# monitoring.net
KiCad netlist of a schematic drawn in Altium Designer
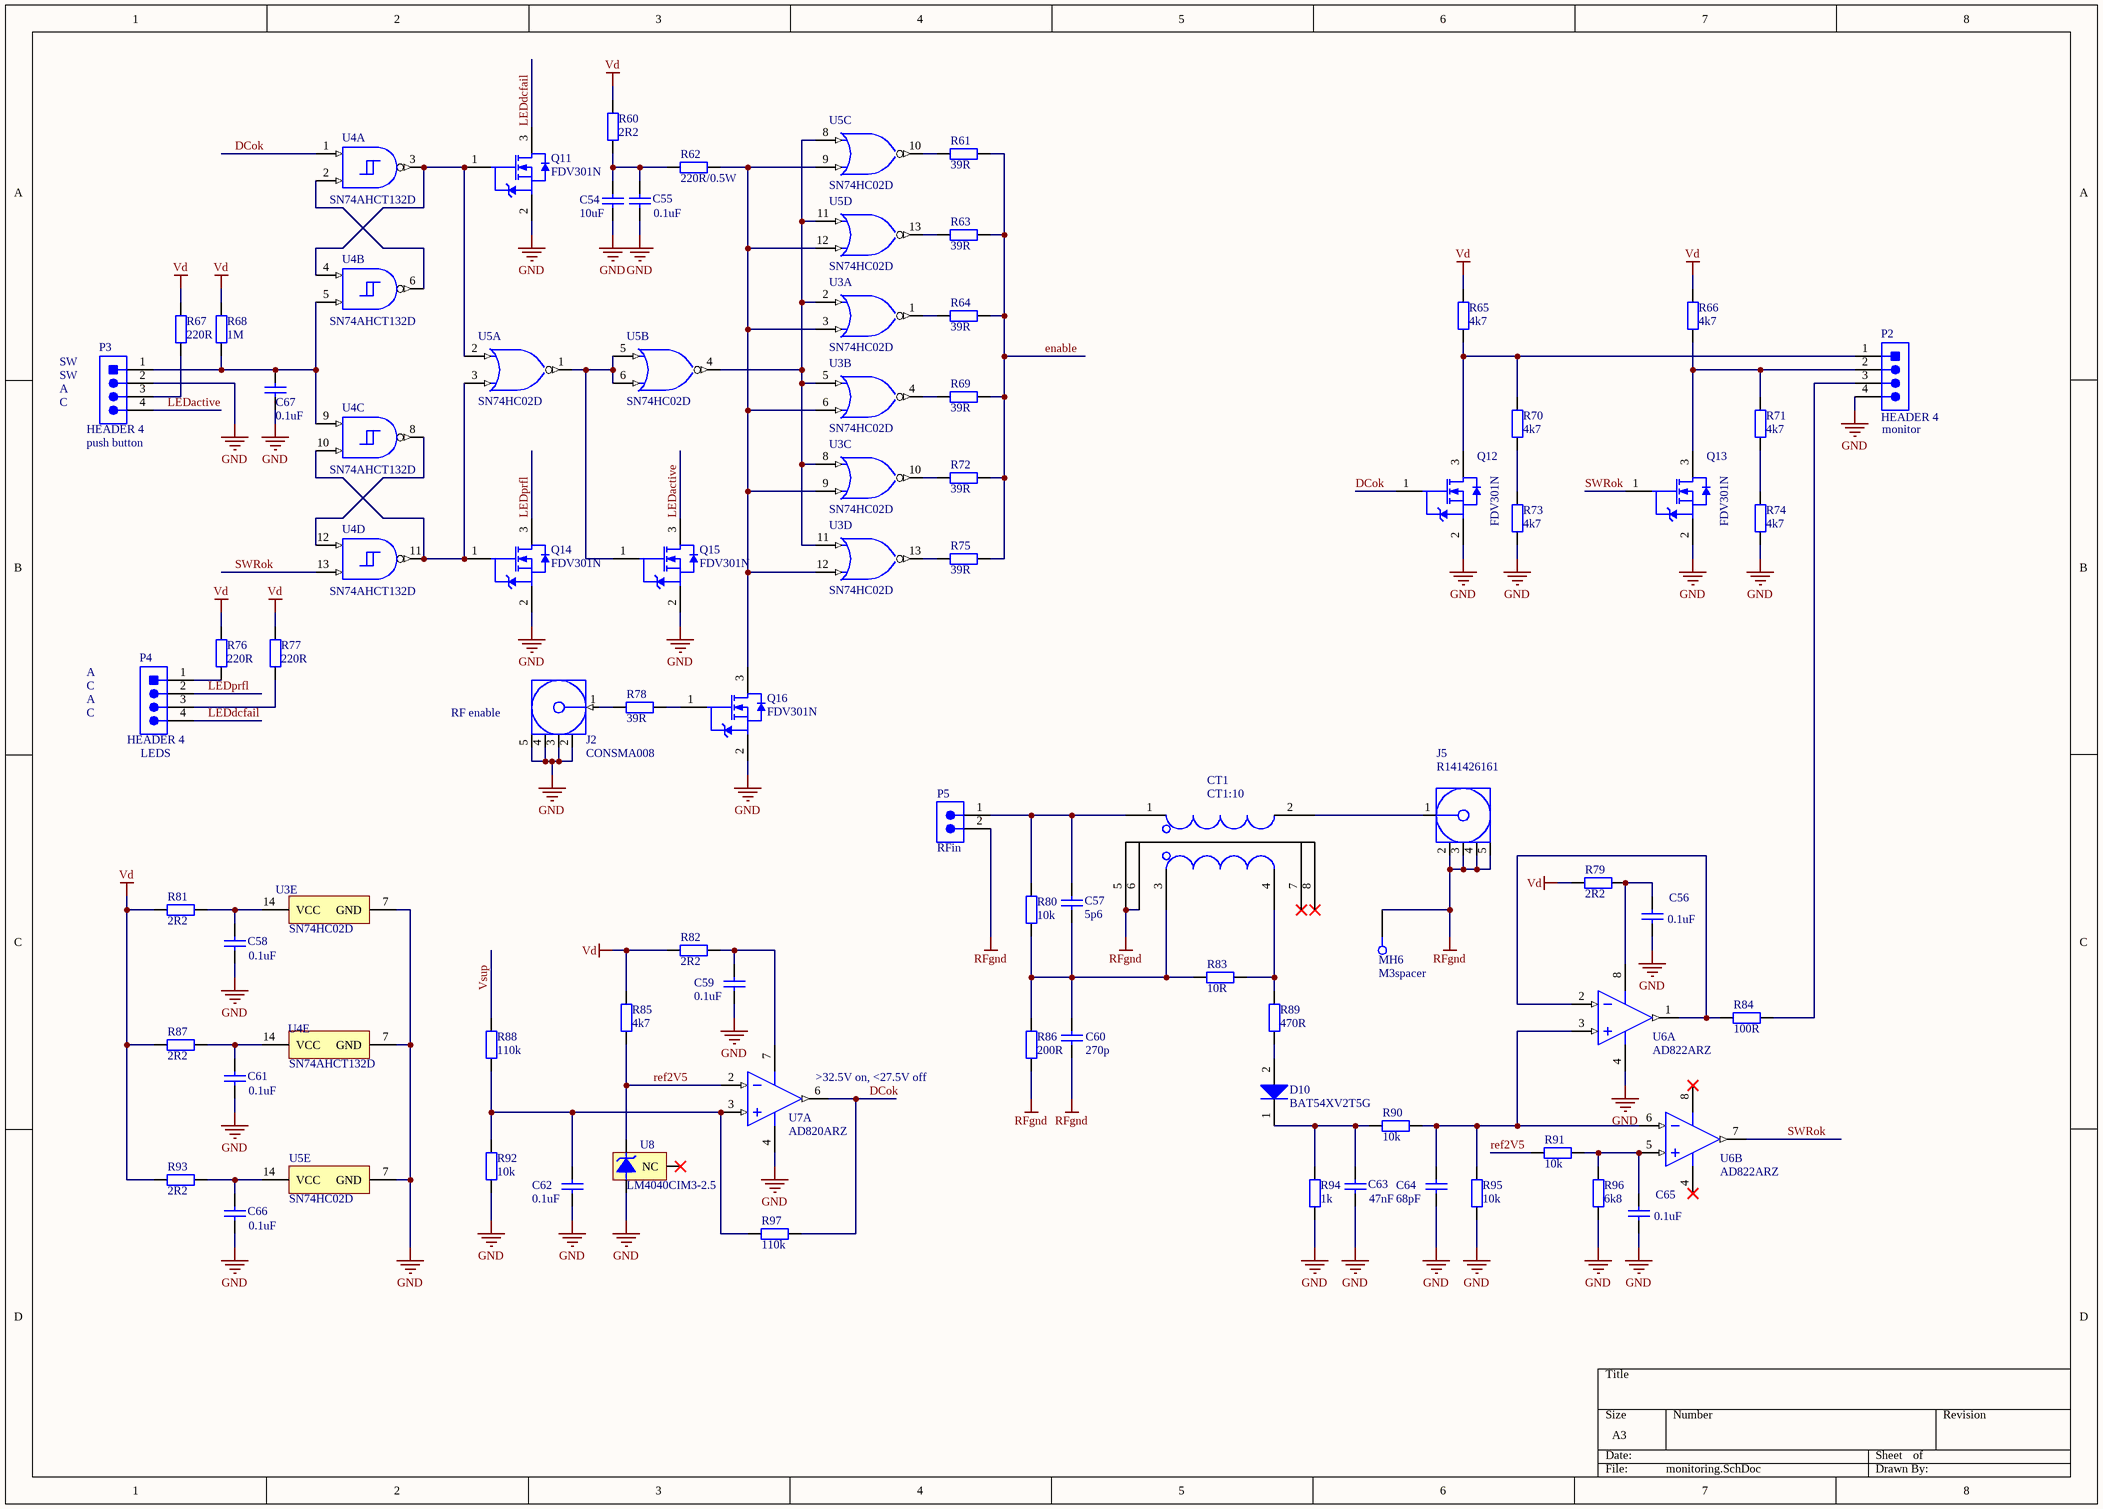
[diagram p0: monitoring.SchDoc]

(export (version "E")
  (design (tool "Eeschema 10.0.6"))
  (components
    (comp (ref "C54")
      (value "10uF")
      (footprint "sm:SM/C_1210")
      (description "Capacitor")
      (fields (field (name "Comment") "Cap") (field (name "PUBLISHER") "Altium Limited"))
      (libsource (lib "Miscellaneous Devices") (part "Cap"))
    )
    (comp (ref "C55")
      (value "0.1uF")
      (footprint "sm:SM/C_0805")
      (description "Capacitor")
      (fields (field (name "Comment") "Cap") (field (name "PUBLISHER") "Altium Limited"))
      (libsource (lib "Miscellaneous Devices") (part "Cap"))
    )
    (comp (ref "C56")
      (value "0.1uF")
      (footprint "sm:SM/C_0805")
      (description "Capacitor")
      (fields (field (name "Comment") "Cap") (field (name "PUBLISHER") "Altium Limited"))
      (libsource (lib "Miscellaneous Devices") (part "Cap"))
    )
    (comp (ref "C57")
      (value "5p6")
      (footprint "sm:SM/C_1206")
      (description "Capacitor")
      (fields (field (name "Comment") "Cap") (field (name "PUBLISHER") "Altium Limited"))
      (libsource (lib "Miscellaneous Devices") (part "Cap"))
    )
    (comp (ref "C58")
      (value "0.1uF")
      (footprint "sm:SM/C_0805")
      (description "Capacitor")
      (fields (field (name "Comment") "Cap") (field (name "PUBLISHER") "Altium Limited"))
      (libsource (lib "Miscellaneous Devices") (part "Cap"))
    )
    (comp (ref "C59")
      (value "0.1uF")
      (footprint "sm:SM/C_0805")
      (description "Capacitor")
      (fields (field (name "Comment") "Cap") (field (name "PUBLISHER") "Altium Limited"))
      (libsource (lib "Miscellaneous Devices") (part "Cap"))
    )
    (comp (ref "C60")
      (value "270p")
      (footprint "sm:SM/C_0805")
      (description "Capacitor")
      (fields (field (name "Comment") "Cap") (field (name "PUBLISHER") "Altium Limited"))
      (libsource (lib "Miscellaneous Devices") (part "Cap"))
    )
    (comp (ref "C61")
      (value "0.1uF")
      (footprint "sm:SM/C_0805")
      (description "Capacitor")
      (fields (field (name "Comment") "Cap") (field (name "PUBLISHER") "Altium Limited"))
      (libsource (lib "Miscellaneous Devices") (part "Cap"))
    )
    (comp (ref "C62")
      (value "0.1uF")
      (footprint "sm:SM/C_0805")
      (description "Capacitor")
      (fields (field (name "Comment") "Cap") (field (name "PUBLISHER") "Altium Limited"))
      (libsource (lib "Miscellaneous Devices") (part "Cap"))
    )
    (comp (ref "C63")
      (value "47nF")
      (footprint "sm:SM/C_0805")
      (description "Capacitor")
      (fields (field (name "Comment") "Cap") (field (name "PUBLISHER") "Altium Limited"))
      (libsource (lib "Miscellaneous Devices") (part "Cap"))
    )
    (comp (ref "C64")
      (value "68pF")
      (footprint "sm:SM/C_0805")
      (description "Capacitor")
      (fields (field (name "Comment") "Cap") (field (name "PUBLISHER") "Altium Limited"))
      (libsource (lib "Miscellaneous Devices") (part "Cap"))
    )
    (comp (ref "C65")
      (value "0.1uF")
      (footprint "sm:SM/C_0805")
      (description "Capacitor")
      (fields (field (name "Comment") "Cap") (field (name "PUBLISHER") "Altium Limited"))
      (libsource (lib "Miscellaneous Devices") (part "Cap"))
    )
    (comp (ref "C66")
      (value "0.1uF")
      (footprint "sm:SM/C_0805")
      (description "Capacitor")
      (fields (field (name "Comment") "Cap") (field (name "PUBLISHER") "Altium Limited"))
      (libsource (lib "Miscellaneous Devices") (part "Cap"))
    )
    (comp (ref "C67")
      (value "0.1uF")
      (footprint "sm:SM/C_0805")
      (description "Capacitor")
      (fields (field (name "Comment") "Cap") (field (name "PUBLISHER") "Altium Limited"))
      (libsource (lib "Miscellaneous Devices") (part "Cap"))
    )
    (comp (ref "CT1") (value "CT1:10") (libsource (lib "stroomtrafo") (part "Component_1")))
    (comp (ref "D10")
      (value "BAT54XV2T5G")
      (footprint "ONSC-SOD-523-2-502-01_V")
      (description "Schottky Barrier Diode, 2-Pin SOD-523, Pb-Free, Tape and Reel")
      (fields (field (name "MANUFACTURER") "On Semiconductor"))
      (libsource (lib "Altium Content Vault") (part "CMP-1055-00490-1"))
    )
    (comp (ref "J2")
      (value "CONSMA008")
      (footprint "Footprint Library:SMA-Grotere-Gaten")
      (description "SMA Female PCB Mount Connector - Extended")
      (libsource (lib "altium-import") (part "root_0_mirrored_CMP-0168-00003-1_"))
    )
    (comp (ref "J5")
      (value "R141426161")
      (footprint "Footprint Library:BNC_Danny")
      (description "Jack BNC Connector, 1 Position, Height 16.26 mm, Tail Length 6.35 mm, -55 to 85 degC, RoHS, Tube")
      (fields (field (name "MANUFACTURER") "TE Connectivity"))
      (libsource (lib "altium-import") (part "root_0_CMP-2000-05627-1_"))
    )
    (comp (ref "MH6")
      (value "M3spacer")
      (footprint "CSTEMP:MTHOLE3.2MM_TOPBOT7MM")
      (description "Mounting Hole, Embedded System Module, 3.2mm pad, 2.7mm plated hole, Top / Bottom copper regions")
      (fields (field (name "PUBLISHER") "Altium"))
      (libsource (lib "altium-import") (part "root_2_MH_"))
    )
    (comp (ref "P2")
      (value "HEADER 4")
      (footprint "pcon100t:POLCON.100/VH/TM1SQS/W.300/4")
      (libsource (lib "altium-import") (part "root_0_CMP-1755-00007-1_"))
    )
    (comp (ref "P3")
      (value "HEADER 4")
      (footprint "pcon100t:POLCON.100/VH/TM1SQS/W.300/4")
      (libsource (lib "altium-import") (part "root_0_mirrored_CMP-1755-00007-1_"))
    )
    (comp (ref "P4")
      (value "HEADER 4")
      (footprint "pcon100t:POLCON.100/VH/TM1SQS/W.300/4")
      (libsource (lib "altium-import") (part "root_0_mirrored_CMP-1755-00007-1_"))
    )
    (comp (ref "P5")
      (value "RFin")
      (footprint "MRIamp:megaheader")
      (fields
        (field (name "MANUFACTURER") "GCT")
        (field (name "PARTNUMBER") "BG055-02-A-1-0650-0530-0350-L-B")
      )
      (libsource (lib "altium-import") (part "root_3_mirrored_CMP-0815-00001-1_"))
    )
    (comp (ref "Q11")
      (value "FDV301N")
      (footprint "FAIR-SOT23-3_V")
      (description "Digital FET, N-Channel, 0.35 W, 25 V, -55 to 150 degC, 3-Pin SOT23, RoHS, Tape and Reel")
      (fields (field (name "MANUFACTURER") "Fairchild"))
      (libsource (lib "Altium Content Vault") (part "CMP-2000-04935-1"))
    )
    (comp (ref "Q12")
      (value "FDV301N")
      (footprint "FAIR-SOT23-3_V")
      (description "Digital FET, N-Channel, 0.35 W, 25 V, -55 to 150 degC, 3-Pin SOT23, RoHS, Tape and Reel")
      (fields (field (name "MANUFACTURER") "Fairchild"))
      (libsource (lib "Altium Content Vault") (part "CMP-2000-04935-1"))
    )
    (comp (ref "Q13")
      (value "FDV301N")
      (footprint "FAIR-SOT23-3_V")
      (description "Digital FET, N-Channel, 0.35 W, 25 V, -55 to 150 degC, 3-Pin SOT23, RoHS, Tape and Reel")
      (fields (field (name "MANUFACTURER") "Fairchild"))
      (libsource (lib "Altium Content Vault") (part "CMP-2000-04935-1"))
    )
    (comp (ref "Q14")
      (value "FDV301N")
      (footprint "FAIR-SOT23-3_V")
      (description "Digital FET, N-Channel, 0.35 W, 25 V, -55 to 150 degC, 3-Pin SOT23, RoHS, Tape and Reel")
      (fields (field (name "MANUFACTURER") "Fairchild"))
      (libsource (lib "Altium Content Vault") (part "CMP-2000-04935-1"))
    )
    (comp (ref "Q15")
      (value "FDV301N")
      (footprint "FAIR-SOT23-3_V")
      (description "Digital FET, N-Channel, 0.35 W, 25 V, -55 to 150 degC, 3-Pin SOT23, RoHS, Tape and Reel")
      (fields (field (name "MANUFACTURER") "Fairchild"))
      (libsource (lib "Altium Content Vault") (part "CMP-2000-04935-1"))
    )
    (comp (ref "Q16")
      (value "FDV301N")
      (footprint "FAIR-SOT23-3_V")
      (description "Digital FET, N-Channel, 0.35 W, 25 V, -55 to 150 degC, 3-Pin SOT23, RoHS, Tape and Reel")
      (fields (field (name "MANUFACTURER") "Fairchild"))
      (libsource (lib "Altium Content Vault") (part "CMP-2000-04935-1"))
    )
    (comp (ref "R60")
      (value "2R2")
      (footprint "sm:SM/R_0805")
      (description "Resistor")
      (fields (field (name "Comment") "Res2") (field (name "PUBLISHER") "Altium Limited"))
      (libsource (lib "Miscellaneous Devices") (part "Res2"))
    )
    (comp (ref "R61")
      (value "39R")
      (footprint "sm:SM/R_0805")
      (description "Resistor")
      (fields (field (name "Comment") "Res2") (field (name "PUBLISHER") "Altium Limited"))
      (libsource (lib "") (part "Res2_2"))
    )
    (comp (ref "R62")
      (value "220R/0.5W")
      (footprint "sm:SM/R_1210")
      (description "Resistor")
      (fields (field (name "Comment") "Res2") (field (name "PUBLISHER") "Altium Limited"))
      (libsource (lib "") (part "Res2_1"))
    )
    (comp (ref "R63")
      (value "39R")
      (footprint "sm:SM/R_0805")
      (description "Resistor")
      (fields (field (name "Comment") "Res2") (field (name "PUBLISHER") "Altium Limited"))
      (libsource (lib "") (part "Res2_2"))
    )
    (comp (ref "R64")
      (value "39R")
      (footprint "sm:SM/R_0805")
      (description "Resistor")
      (fields (field (name "Comment") "Res2") (field (name "PUBLISHER") "Altium Limited"))
      (libsource (lib "") (part "Res2_2"))
    )
    (comp (ref "R65")
      (value "4k7")
      (footprint "sm:SM/R_0805")
      (description "Resistor")
      (fields (field (name "Comment") "Res2") (field (name "PUBLISHER") "Altium Limited"))
      (libsource (lib "Miscellaneous Devices") (part "Res2"))
    )
    (comp (ref "R66")
      (value "4k7")
      (footprint "sm:SM/R_0805")
      (description "Resistor")
      (fields (field (name "Comment") "Res2") (field (name "PUBLISHER") "Altium Limited"))
      (libsource (lib "Miscellaneous Devices") (part "Res2"))
    )
    (comp (ref "R67")
      (value "220R")
      (footprint "sm:SM/C_1206")
      (description "Resistor")
      (fields (field (name "Comment") "Res2") (field (name "PUBLISHER") "Altium Limited"))
      (libsource (lib "Miscellaneous Devices") (part "Res2"))
    )
    (comp (ref "R68")
      (value "1M")
      (footprint "sm:SM/R_0805")
      (description "Resistor")
      (fields (field (name "Comment") "Res2") (field (name "PUBLISHER") "Altium Limited"))
      (libsource (lib "Miscellaneous Devices") (part "Res2"))
    )
    (comp (ref "R69")
      (value "39R")
      (footprint "sm:SM/R_0805")
      (description "Resistor")
      (fields (field (name "Comment") "Res2") (field (name "PUBLISHER") "Altium Limited"))
      (libsource (lib "") (part "Res2_2"))
    )
    (comp (ref "R70")
      (value "4k7")
      (footprint "sm:SM/R_0805")
      (description "Resistor")
      (fields (field (name "Comment") "Res2") (field (name "PUBLISHER") "Altium Limited"))
      (libsource (lib "Miscellaneous Devices") (part "Res2"))
    )
    (comp (ref "R71")
      (value "4k7")
      (footprint "sm:SM/R_0805")
      (description "Resistor")
      (fields (field (name "Comment") "Res2") (field (name "PUBLISHER") "Altium Limited"))
      (libsource (lib "Miscellaneous Devices") (part "Res2"))
    )
    (comp (ref "R72")
      (value "39R")
      (footprint "sm:SM/R_0805")
      (description "Resistor")
      (fields (field (name "Comment") "Res2") (field (name "PUBLISHER") "Altium Limited"))
      (libsource (lib "") (part "Res2_2"))
    )
    (comp (ref "R73")
      (value "4k7")
      (footprint "sm:SM/R_0805")
      (description "Resistor")
      (fields (field (name "Comment") "Res2") (field (name "PUBLISHER") "Altium Limited"))
      (libsource (lib "Miscellaneous Devices") (part "Res2"))
    )
    (comp (ref "R74")
      (value "4k7")
      (footprint "sm:SM/R_0805")
      (description "Resistor")
      (fields (field (name "Comment") "Res2") (field (name "PUBLISHER") "Altium Limited"))
      (libsource (lib "Miscellaneous Devices") (part "Res2"))
    )
    (comp (ref "R75")
      (value "39R")
      (footprint "sm:SM/R_0805")
      (description "Resistor")
      (fields (field (name "Comment") "Res2") (field (name "PUBLISHER") "Altium Limited"))
      (libsource (lib "") (part "Res2_2"))
    )
    (comp (ref "R76")
      (value "220R")
      (footprint "sm:SM/C_1206")
      (description "Resistor")
      (fields (field (name "Comment") "Res2") (field (name "PUBLISHER") "Altium Limited"))
      (libsource (lib "Miscellaneous Devices") (part "Res2"))
    )
    (comp (ref "R77")
      (value "220R")
      (footprint "sm:SM/C_1206")
      (description "Resistor")
      (fields (field (name "Comment") "Res2") (field (name "PUBLISHER") "Altium Limited"))
      (libsource (lib "Miscellaneous Devices") (part "Res2"))
    )
    (comp (ref "R78")
      (value "39R")
      (footprint "sm:SM/R_0805")
      (description "Resistor")
      (fields (field (name "Comment") "Res2") (field (name "PUBLISHER") "Altium Limited"))
      (libsource (lib "") (part "Res2_2"))
    )
    (comp (ref "R79")
      (value "2R2")
      (footprint "sm:SM/R_0805")
      (description "Resistor")
      (fields (field (name "Comment") "Res2") (field (name "PUBLISHER") "Altium Limited"))
      (libsource (lib "") (part "Res2_2"))
    )
    (comp (ref "R80")
      (value "10k")
      (footprint "tm_axial:AX/.800X.200/.037")
      (description "Resistor")
      (fields (field (name "Comment") "Res2") (field (name "PUBLISHER") "Altium Limited"))
      (libsource (lib "Miscellaneous Devices") (part "Res2"))
    )
    (comp (ref "R81")
      (value "2R2")
      (footprint "sm:SM/R_0805")
      (description "Resistor")
      (fields (field (name "Comment") "Res2") (field (name "PUBLISHER") "Altium Limited"))
      (libsource (lib "") (part "Res2_2"))
    )
    (comp (ref "R82")
      (value "2R2")
      (footprint "sm:SM/R_0805")
      (description "Resistor")
      (fields (field (name "Comment") "Res2") (field (name "PUBLISHER") "Altium Limited"))
      (libsource (lib "") (part "Res2_2"))
    )
    (comp (ref "R83")
      (value "10R")
      (footprint "tm_axial:AX/.800X.200/.037")
      (description "Resistor")
      (fields (field (name "Comment") "Res2") (field (name "PUBLISHER") "Altium Limited"))
      (libsource (lib "") (part "Res2_1"))
    )
    (comp (ref "R84")
      (value "100R")
      (footprint "sm:SM/C_1206")
      (description "Resistor")
      (fields (field (name "Comment") "Res2") (field (name "PUBLISHER") "Altium Limited"))
      (libsource (lib "") (part "Res2_1"))
    )
    (comp (ref "R85")
      (value "4k7")
      (footprint "sm:SM/R_0805")
      (description "Resistor")
      (fields (field (name "Comment") "Res2") (field (name "PUBLISHER") "Altium Limited"))
      (libsource (lib "Miscellaneous Devices") (part "Res2"))
    )
    (comp (ref "R86")
      (value "200R")
      (footprint "tm_axial:AX/.550X.150/.034")
      (description "Resistor")
      (fields (field (name "Comment") "Res2") (field (name "PUBLISHER") "Altium Limited"))
      (libsource (lib "Miscellaneous Devices") (part "Res2"))
    )
    (comp (ref "R87")
      (value "2R2")
      (footprint "sm:SM/R_0805")
      (description "Resistor")
      (fields (field (name "Comment") "Res2") (field (name "PUBLISHER") "Altium Limited"))
      (libsource (lib "") (part "Res2_2"))
    )
    (comp (ref "R88")
      (value "110k")
      (footprint "sm:SM/R_0805")
      (description "Resistor")
      (fields (field (name "Comment") "Res2") (field (name "PUBLISHER") "Altium Limited"))
      (libsource (lib "Miscellaneous Devices") (part "Res2"))
    )
    (comp (ref "R89")
      (value "470R")
      (footprint "sm:SM/R_0805")
      (description "Resistor")
      (fields (field (name "Comment") "Res2") (field (name "PUBLISHER") "Altium Limited"))
      (libsource (lib "Miscellaneous Devices") (part "Res2"))
    )
    (comp (ref "R90")
      (value "10k")
      (footprint "sm:SM/R_0805")
      (description "Resistor")
      (fields (field (name "Comment") "Res2") (field (name "PUBLISHER") "Altium Limited"))
      (libsource (lib "") (part "Res2_2"))
    )
    (comp (ref "R91")
      (value "10k")
      (footprint "sm:SM/R_0805")
      (description "Resistor")
      (fields (field (name "Comment") "Res2") (field (name "PUBLISHER") "Altium Limited"))
      (libsource (lib "") (part "Res2_2"))
    )
    (comp (ref "R92")
      (value "10k")
      (footprint "sm:SM/R_0805")
      (description "Resistor")
      (fields (field (name "Comment") "Res2") (field (name "PUBLISHER") "Altium Limited"))
      (libsource (lib "Miscellaneous Devices") (part "Res2"))
    )
    (comp (ref "R93")
      (value "2R2")
      (footprint "sm:SM/R_0805")
      (description "Resistor")
      (fields (field (name "Comment") "Res2") (field (name "PUBLISHER") "Altium Limited"))
      (libsource (lib "") (part "Res2_2"))
    )
    (comp (ref "R94")
      (value "1k")
      (footprint "sm:SM/R_0805")
      (description "Resistor")
      (fields (field (name "Comment") "Res2") (field (name "PUBLISHER") "Altium Limited"))
      (libsource (lib "Miscellaneous Devices") (part "Res2"))
    )
    (comp (ref "R95")
      (value "10k")
      (footprint "sm:SM/R_0805")
      (description "Resistor")
      (fields (field (name "Comment") "Res2") (field (name "PUBLISHER") "Altium Limited"))
      (libsource (lib "") (part "Res2_3"))
    )
    (comp (ref "R96")
      (value "6k8")
      (footprint "sm:SM/R_0805")
      (description "Resistor")
      (fields (field (name "Comment") "Res2") (field (name "PUBLISHER") "Altium Limited"))
      (libsource (lib "") (part "Res2_3"))
    )
    (comp (ref "R97")
      (value "110k")
      (footprint "sm:SM/R_0805")
      (description "Resistor")
      (fields (field (name "Comment") "Res2") (field (name "PUBLISHER") "Altium Limited"))
      (libsource (lib "") (part "Res2_2"))
    )
    (comp (ref "U3")
      (value "SN74HC02D")
      (footprint "D0014A_N")
      (description "Quadruple 2-Input Positive-NOR Gates, D0014A, TUBE")
      (fields
        (field (name "GENERIC PART NUMBER") "SN74HC02")
        (field (name "MANUFACTURER") "Texas Instruments")
      )
      (libsource (lib "Altium Content Vault") (part "CMP-0806-00060-3"))
    )
    (comp (ref "U4")
      (value "SN74AHCT132D")
      (footprint "D0014A_L")
      (description "Quadruple Positive-NAND Gates With Schmitt-Trigger Inputs, D0014A, TUBE")
      (fields
        (field (name "GENERIC PART NUMBER") "SN74AHCT132")
        (field (name "MANUFACTURER") "Texas Instruments")
      )
      (libsource (lib "Altium Content Vault") (part "CMP-1627-00035-3"))
    )
    (comp (ref "U5")
      (value "SN74HC02D")
      (footprint "D0014A_N")
      (description "Quadruple 2-Input Positive-NOR Gates, D0014A, TUBE")
      (fields
        (field (name "GENERIC PART NUMBER") "SN74HC02")
        (field (name "MANUFACTURER") "Texas Instruments")
      )
      (libsource (lib "Altium Content Vault") (part "CMP-0806-00060-3"))
    )
    (comp (ref "U6")
      (value "AD822ARZ")
      (footprint "ADI-R-8_M")
      (fields (field (name "MANUFACTURER") "Analog Devices") (field (name "GENERIC PART NUMBER") "AD822"))
      (libsource (lib "Altium Content Vault") (part "CMP-0384-00785-2"))
    )
    (comp (ref "U7")
      (value "AD820ARZ")
      (footprint "ADI-R-8_L")
      (fields
        (field (name "PARTNUMBER") "AD820ARZ-REEL7")
        (field (name "GENERIC PART NUMBER") "AD820")
        (field (name "MANUFACTURER") "Analog Devices")
      )
      (libsource (lib "Altium Content Vault") (part "CMP-0384-00651-1"))
    )
    (comp (ref "U8")
      (value "LM4040CIM3-2.5")
      (footprint "DBZ0003A_N")
      (description "Precision Micropower Shunt Voltage Reference, 3-pin SOT-23")
      (fields (field (name "MANUFACTURER") "Texas Instruments"))
      (libsource (lib "Altium Content Vault") (part "CMP-0074-00570-3"))
    )
  )
  (nets
    (net (code "1") (name "/DCok") (class "Default")
      (node (ref "Q12") (pin "1") (pinfunction "G_1") (pintype "passive"))
      (node (ref "R97") (pin "2") (pinfunction "2_2") (pintype "passive"))
      (node (ref "U4") (pin "1") (pinfunction "1A_1") (pintype "input"))
      (node (ref "U7") (pin "6") (pinfunction "VOUT_6") (pintype "output"))
    )
    (net (code "2") (name "/LEDactive") (class "Default")
      (node (ref "P3") (pin "4") (pinfunction "4_4") (pintype "passive"))
      (node (ref "Q15") (pin "3") (pinfunction "D_3") (pintype "passive"))
    )
    (net (code "3") (name "/LEDdcfail") (class "Default")
      (node (ref "P4") (pin "4") (pinfunction "4_4") (pintype "passive"))
      (node (ref "Q11") (pin "3") (pinfunction "D_3") (pintype "passive"))
    )
    (net (code "4") (name "/LEDprfl") (class "Default")
      (node (ref "P4") (pin "2") (pinfunction "2_2") (pintype "passive"))
      (node (ref "Q14") (pin "3") (pinfunction "D_3") (pintype "passive"))
    )
    (net (code "5") (name "/SWRok") (class "Default")
      (node (ref "Q13") (pin "1") (pinfunction "G_1") (pintype "passive"))
      (node (ref "U4") (pin "13") (pinfunction "4B_13") (pintype "input"))
      (node (ref "U6") (pin "7") (pinfunction "OUT_2_7") (pintype "output"))
    )
    (net (code "6") (name "/Vsup") (class "Default")
      (node (ref "R88") (pin "1") (pinfunction "1_1") (pintype "passive"))
    )
    (net (code "7") (name "/enable") (class "Default")
      (node (ref "R61") (pin "2") (pinfunction "2_2") (pintype "passive"))
      (node (ref "R63") (pin "2") (pinfunction "2_2") (pintype "passive"))
      (node (ref "R64") (pin "2") (pinfunction "2_2") (pintype "passive"))
      (node (ref "R69") (pin "2") (pinfunction "2_2") (pintype "passive"))
      (node (ref "R72") (pin "2") (pinfunction "2_2") (pintype "passive"))
      (node (ref "R75") (pin "2") (pinfunction "2_2") (pintype "passive"))
    )
    (net (code "8") (name "/ref2V5") (class "Default")
      (node (ref "R85") (pin "2") (pinfunction "2_2") (pintype "passive"))
      (node (ref "R91") (pin "1") (pinfunction "1_1") (pintype "passive"))
      (node (ref "U7") (pin "2") (pinfunction "-IN_2") (pintype "input"))
      (node (ref "U8") (pin "1") (pinfunction "+V_1") (pintype "passive"))
    )
    (net (code "9") (name "GND") (class "Default")
      (node (ref "C54") (pin "2") (pinfunction "2_2") (pintype "passive"))
      (node (ref "C55") (pin "1") (pinfunction "1_1") (pintype "passive"))
      (node (ref "C56") (pin "1") (pinfunction "1_1") (pintype "passive"))
      (node (ref "C58") (pin "1") (pinfunction "1_1") (pintype "passive"))
      (node (ref "C59") (pin "1") (pinfunction "1_1") (pintype "passive"))
      (node (ref "C61") (pin "1") (pinfunction "1_1") (pintype "passive"))
      (node (ref "C62") (pin "1") (pinfunction "1_1") (pintype "passive"))
      (node (ref "C63") (pin "1") (pinfunction "1_1") (pintype "passive"))
      (node (ref "C64") (pin "1") (pinfunction "1_1") (pintype "passive"))
      (node (ref "C65") (pin "1") (pinfunction "1_1") (pintype "passive"))
      (node (ref "C66") (pin "1") (pinfunction "1_1") (pintype "passive"))
      (node (ref "C67") (pin "1") (pinfunction "1_1") (pintype "passive"))
      (node (ref "J2") (pin "2") (pinfunction "GND_2") (pintype "power_in"))
      (node (ref "J2") (pin "3") (pinfunction "GND_3") (pintype "power_in"))
      (node (ref "J2") (pin "4") (pinfunction "GND_4") (pintype "power_in"))
      (node (ref "J2") (pin "5") (pinfunction "GND_5") (pintype "power_in"))
      (node (ref "P2") (pin "4") (pinfunction "4_4") (pintype "passive"))
      (node (ref "P3") (pin "2") (pinfunction "2_2") (pintype "passive"))
      (node (ref "Q11") (pin "2") (pinfunction "S_2") (pintype "passive"))
      (node (ref "Q12") (pin "2") (pinfunction "S_2") (pintype "passive"))
      (node (ref "Q13") (pin "2") (pinfunction "S_2") (pintype "passive"))
      (node (ref "Q14") (pin "2") (pinfunction "S_2") (pintype "passive"))
      (node (ref "Q15") (pin "2") (pinfunction "S_2") (pintype "passive"))
      (node (ref "Q16") (pin "2") (pinfunction "S_2") (pintype "passive"))
      (node (ref "R73") (pin "2") (pinfunction "2_2") (pintype "passive"))
      (node (ref "R74") (pin "2") (pinfunction "2_2") (pintype "passive"))
      (node (ref "R92") (pin "2") (pinfunction "2_2") (pintype "passive"))
      (node (ref "R94") (pin "2") (pinfunction "2_2") (pintype "passive"))
      (node (ref "R95") (pin "1") (pinfunction "1_1") (pintype "passive"))
      (node (ref "R96") (pin "1") (pinfunction "1_1") (pintype "passive"))
      (node (ref "U3") (pin "7") (pinfunction "GND_7") (pintype "power_in"))
      (node (ref "U4") (pin "7") (pinfunction "GND_7") (pintype "power_in"))
      (node (ref "U5") (pin "7") (pinfunction "GND_7") (pintype "power_in"))
      (node (ref "U6") (pin "4") (pinfunction "-V_4") (pintype "power_in"))
      (node (ref "U7") (pin "4") (pinfunction "-VS_4") (pintype "power_in"))
      (node (ref "U8") (pin "2") (pinfunction "-V_2") (pintype "passive"))
    )
    (net (code "10") (name "Net-(C54-Pad1)") (class "Default")
      (node (ref "C54") (pin "1") (pinfunction "1_1") (pintype "passive"))
      (node (ref "C55") (pin "2") (pinfunction "2_2") (pintype "passive"))
      (node (ref "R60") (pin "2") (pinfunction "2_2") (pintype "passive"))
      (node (ref "R62") (pin "2") (pinfunction "2_2") (pintype "passive"))
    )
    (net (code "11") (name "Net-(C57-Pad1)") (class "Default")
      (node (ref "C57") (pin "1") (pinfunction "1_1") (pintype "passive"))
      (node (ref "C60") (pin "2") (pinfunction "2_2") (pintype "passive"))
      (node (ref "CT1") (pin "3") (pinfunction "3_3") (pintype "passive"))
      (node (ref "R80") (pin "2") (pinfunction "2_2") (pintype "passive"))
      (node (ref "R83") (pin "2") (pinfunction "2_2") (pintype "passive"))
      (node (ref "R86") (pin "1") (pinfunction "1_1") (pintype "passive"))
    )
    (net (code "12") (name "Net-(C57-Pad2)") (class "Default")
      (node (ref "C57") (pin "2") (pinfunction "2_2") (pintype "passive"))
      (node (ref "CT1") (pin "1") (pinfunction "1_1") (pintype "passive"))
      (node (ref "P5") (pin "1") (pinfunction "1_1") (pintype "passive"))
      (node (ref "R80") (pin "1") (pinfunction "1_1") (pintype "passive"))
    )
    (net (code "13") (name "Net-(CT1-Pad2)") (class "Default")
      (node (ref "CT1") (pin "2") (pinfunction "2_2") (pintype "passive"))
      (node (ref "J5") (pin "1") (pinfunction "1_1") (pintype "passive"))
    )
    (net (code "14") (name "Net-(CT1-Pad4)") (class "Default")
      (node (ref "CT1") (pin "4") (pinfunction "4_4") (pintype "passive"))
      (node (ref "R83") (pin "1") (pinfunction "1_1") (pintype "passive"))
      (node (ref "R89") (pin "1") (pinfunction "1_1") (pintype "passive"))
    )
    (net (code "15") (name "Net-(D10-A)") (class "Default")
      (node (ref "D10") (pin "2") (pinfunction "A_2") (pintype "passive"))
      (node (ref "R89") (pin "2") (pinfunction "2_2") (pintype "passive"))
    )
    (net (code "16") (name "Net-(D10-K)") (class "Default")
      (node (ref "C63") (pin "2") (pinfunction "2_2") (pintype "passive"))
      (node (ref "D10") (pin "1") (pinfunction "K_1") (pintype "passive"))
      (node (ref "R90") (pin "1") (pinfunction "1_1") (pintype "passive"))
      (node (ref "R94") (pin "1") (pinfunction "1_1") (pintype "passive"))
    )
    (net (code "17") (name "Net-(J2-Signal)") (class "Default")
      (node (ref "J2") (pin "1") (pinfunction "Signal_1") (pintype "input"))
      (node (ref "R78") (pin "1") (pinfunction "1_1") (pintype "passive"))
    )
    (net (code "18") (name "Net-(P2-Pad3)") (class "Default")
      (node (ref "P2") (pin "3") (pinfunction "3_3") (pintype "passive"))
      (node (ref "R84") (pin "1") (pinfunction "1_1") (pintype "passive"))
    )
    (net (code "19") (name "Net-(P3-Pad3)") (class "Default")
      (node (ref "P3") (pin "3") (pinfunction "3_3") (pintype "passive"))
      (node (ref "R67") (pin "2") (pinfunction "2_2") (pintype "passive"))
    )
    (net (code "20") (name "Net-(P4-Pad1)") (class "Default")
      (node (ref "P4") (pin "1") (pinfunction "1_1") (pintype "passive"))
      (node (ref "R76") (pin "2") (pinfunction "2_2") (pintype "passive"))
    )
    (net (code "21") (name "Net-(P4-Pad3)") (class "Default")
      (node (ref "P4") (pin "3") (pinfunction "3_3") (pintype "passive"))
      (node (ref "R77") (pin "2") (pinfunction "2_2") (pintype "passive"))
    )
    (net (code "22") (name "Net-(Q11-G)") (class "Default")
      (node (ref "Q11") (pin "1") (pinfunction "G_1") (pintype "passive"))
      (node (ref "U4") (pin "3") (pinfunction "1Y_3") (pintype "output"))
      (node (ref "U4") (pin "4") (pinfunction "2A_4") (pintype "input"))
      (node (ref "U5") (pin "2") (pinfunction "1A_2") (pintype "input"))
    )
    (net (code "23") (name "Net-(Q12-D)") (class "Default")
      (node (ref "P2") (pin "1") (pinfunction "1_1") (pintype "passive"))
      (node (ref "Q12") (pin "3") (pinfunction "D_3") (pintype "passive"))
      (node (ref "R65") (pin "2") (pinfunction "2_2") (pintype "passive"))
      (node (ref "R70") (pin "1") (pinfunction "1_1") (pintype "passive"))
    )
    (net (code "24") (name "Net-(Q13-D)") (class "Default")
      (node (ref "P2") (pin "2") (pinfunction "2_2") (pintype "passive"))
      (node (ref "Q13") (pin "3") (pinfunction "D_3") (pintype "passive"))
      (node (ref "R66") (pin "2") (pinfunction "2_2") (pintype "passive"))
      (node (ref "R71") (pin "1") (pinfunction "1_1") (pintype "passive"))
    )
    (net (code "25") (name "Net-(Q14-G)") (class "Default")
      (node (ref "Q14") (pin "1") (pinfunction "G_1") (pintype "passive"))
      (node (ref "U4") (pin "10") (pinfunction "3B_10") (pintype "input"))
      (node (ref "U4") (pin "11") (pinfunction "4Y_11") (pintype "output"))
      (node (ref "U5") (pin "3") (pinfunction "1B_3") (pintype "input"))
    )
    (net (code "26") (name "Net-(Q15-G)") (class "Default")
      (node (ref "Q15") (pin "1") (pinfunction "G_1") (pintype "passive"))
      (node (ref "U5") (pin "1") (pinfunction "1Y_1") (pintype "output"))
      (node (ref "U5") (pin "5") (pinfunction "2A_5") (pintype "input"))
      (node (ref "U5") (pin "6") (pinfunction "2B_6") (pintype "input"))
    )
    (net (code "27") (name "Net-(Q16-D)") (class "Default")
      (node (ref "Q16") (pin "3") (pinfunction "D_3") (pintype "passive"))
      (node (ref "R62") (pin "1") (pinfunction "1_1") (pintype "passive"))
      (node (ref "U3") (pin "12") (pinfunction "4B_12") (pintype "input"))
      (node (ref "U3") (pin "3") (pinfunction "1B_3") (pintype "input"))
      (node (ref "U3") (pin "6") (pinfunction "2B_6") (pintype "input"))
      (node (ref "U3") (pin "9") (pinfunction "3B_9") (pintype "input"))
      (node (ref "U5") (pin "12") (pinfunction "4B_12") (pintype "input"))
      (node (ref "U5") (pin "9") (pinfunction "3B_9") (pintype "input"))
    )
    (net (code "28") (name "Net-(Q16-G)") (class "Default")
      (node (ref "Q16") (pin "1") (pinfunction "G_1") (pintype "passive"))
      (node (ref "R78") (pin "2") (pinfunction "2_2") (pintype "passive"))
    )
    (net (code "29") (name "Net-(R70-Pad2)") (class "Default")
      (node (ref "R70") (pin "2") (pinfunction "2_2") (pintype "passive"))
      (node (ref "R73") (pin "1") (pinfunction "1_1") (pintype "passive"))
    )
    (net (code "30") (name "Net-(R71-Pad2)") (class "Default")
      (node (ref "R71") (pin "2") (pinfunction "2_2") (pintype "passive"))
      (node (ref "R74") (pin "1") (pinfunction "1_1") (pintype "passive"))
    )
    (net (code "31") (name "Net-(U3A-1A)") (class "Default")
      (node (ref "U3") (pin "11") (pinfunction "4A_11") (pintype "input"))
      (node (ref "U3") (pin "2") (pinfunction "1A_2") (pintype "input"))
      (node (ref "U3") (pin "5") (pinfunction "2A_5") (pintype "input"))
      (node (ref "U3") (pin "8") (pinfunction "3A_8") (pintype "input"))
      (node (ref "U5") (pin "11") (pinfunction "4A_11") (pintype "input"))
      (node (ref "U5") (pin "4") (pinfunction "2Y_4") (pintype "output"))
      (node (ref "U5") (pin "8") (pinfunction "3A_8") (pintype "input"))
    )
    (net (code "32") (name "Net-(U3A-1Y)") (class "Default")
      (node (ref "R64") (pin "1") (pinfunction "1_1") (pintype "passive"))
      (node (ref "U3") (pin "1") (pinfunction "1Y_1") (pintype "output"))
    )
    (net (code "33") (name "Net-(U3B-2Y)") (class "Default")
      (node (ref "R69") (pin "1") (pinfunction "1_1") (pintype "passive"))
      (node (ref "U3") (pin "4") (pinfunction "2Y_4") (pintype "output"))
    )
    (net (code "34") (name "Net-(U3C-3Y)") (class "Default")
      (node (ref "R72") (pin "1") (pinfunction "1_1") (pintype "passive"))
      (node (ref "U3") (pin "10") (pinfunction "3Y_10") (pintype "output"))
    )
    (net (code "35") (name "Net-(U3D-4Y)") (class "Default")
      (node (ref "R75") (pin "1") (pinfunction "1_1") (pintype "passive"))
      (node (ref "U3") (pin "13") (pinfunction "4Y_13") (pintype "output"))
    )
    (net (code "36") (name "Net-(U3E-VCC)") (class "Default")
      (node (ref "C58") (pin "2") (pinfunction "2_2") (pintype "passive"))
      (node (ref "R81") (pin "2") (pinfunction "2_2") (pintype "passive"))
      (node (ref "U3") (pin "14") (pinfunction "VCC_14") (pintype "power_in"))
    )
    (net (code "37") (name "Net-(U4A-1B)") (class "Default")
      (node (ref "U4") (pin "2") (pinfunction "1B_2") (pintype "input"))
      (node (ref "U4") (pin "6") (pinfunction "2Y_6") (pintype "output"))
    )
    (net (code "38") (name "Net-(U4B-2B)") (class "Default")
      (node (ref "C67") (pin "2") (pinfunction "2_2") (pintype "passive"))
      (node (ref "P3") (pin "1") (pinfunction "1_1") (pintype "passive"))
      (node (ref "R68") (pin "2") (pinfunction "2_2") (pintype "passive"))
      (node (ref "U4") (pin "5") (pinfunction "2B_5") (pintype "input"))
      (node (ref "U4") (pin "9") (pinfunction "3A_9") (pintype "input"))
    )
    (net (code "39") (name "Net-(U4C-3Y)") (class "Default")
      (node (ref "U4") (pin "12") (pinfunction "4A_12") (pintype "input"))
      (node (ref "U4") (pin "8") (pinfunction "3Y_8") (pintype "output"))
    )
    (net (code "40") (name "Net-(U4E-VCC)") (class "Default")
      (node (ref "C61") (pin "2") (pinfunction "2_2") (pintype "passive"))
      (node (ref "R87") (pin "2") (pinfunction "2_2") (pintype "passive"))
      (node (ref "U4") (pin "14") (pinfunction "VCC_14") (pintype "power_in"))
    )
    (net (code "41") (name "Net-(U5C-3Y)") (class "Default")
      (node (ref "R61") (pin "1") (pinfunction "1_1") (pintype "passive"))
      (node (ref "U5") (pin "10") (pinfunction "3Y_10") (pintype "output"))
    )
    (net (code "42") (name "Net-(U5D-4Y)") (class "Default")
      (node (ref "R63") (pin "1") (pinfunction "1_1") (pintype "passive"))
      (node (ref "U5") (pin "13") (pinfunction "4Y_13") (pintype "output"))
    )
    (net (code "43") (name "Net-(U5E-VCC)") (class "Default")
      (node (ref "C66") (pin "2") (pinfunction "2_2") (pintype "passive"))
      (node (ref "R93") (pin "2") (pinfunction "2_2") (pintype "passive"))
      (node (ref "U5") (pin "14") (pinfunction "VCC_14") (pintype "power_in"))
    )
    (net (code "44") (name "Net-(U6A-+IN_1)") (class "Default")
      (node (ref "C64") (pin "2") (pinfunction "2_2") (pintype "passive"))
      (node (ref "R90") (pin "2") (pinfunction "2_2") (pintype "passive"))
      (node (ref "R95") (pin "2") (pinfunction "2_2") (pintype "passive"))
      (node (ref "U6") (pin "3") (pinfunction "+IN_1_3") (pintype "input"))
      (node (ref "U6") (pin "6") (pinfunction "-IN_2_6") (pintype "input"))
    )
    (net (code "45") (name "Net-(U6A-+V)") (class "Default")
      (node (ref "C56") (pin "2") (pinfunction "2_2") (pintype "passive"))
      (node (ref "R79") (pin "2") (pinfunction "2_2") (pintype "passive"))
      (node (ref "U6") (pin "8") (pinfunction "+V_8") (pintype "power_in"))
    )
    (net (code "46") (name "Net-(U6A--IN_1)") (class "Default")
      (node (ref "R84") (pin "2") (pinfunction "2_2") (pintype "passive"))
      (node (ref "U6") (pin "1") (pinfunction "OUT_1_1") (pintype "output"))
      (node (ref "U6") (pin "2") (pinfunction "-IN_1_2") (pintype "input"))
    )
    (net (code "47") (name "Net-(U6B-+IN_2)") (class "Default")
      (node (ref "C65") (pin "2") (pinfunction "2_2") (pintype "passive"))
      (node (ref "R91") (pin "2") (pinfunction "2_2") (pintype "passive"))
      (node (ref "R96") (pin "2") (pinfunction "2_2") (pintype "passive"))
      (node (ref "U6") (pin "5") (pinfunction "+IN_2_5") (pintype "input"))
    )
    (net (code "48") (name "Net-(U7A-+IN)") (class "Default")
      (node (ref "C62") (pin "2") (pinfunction "2_2") (pintype "passive"))
      (node (ref "R88") (pin "2") (pinfunction "2_2") (pintype "passive"))
      (node (ref "R92") (pin "1") (pinfunction "1_1") (pintype "passive"))
      (node (ref "R97") (pin "1") (pinfunction "1_1") (pintype "passive"))
      (node (ref "U7") (pin "3") (pinfunction "+IN_3") (pintype "input"))
    )
    (net (code "49") (name "Net-(U7A-+VS)") (class "Default")
      (node (ref "C59") (pin "2") (pinfunction "2_2") (pintype "passive"))
      (node (ref "R82") (pin "2") (pinfunction "2_2") (pintype "passive"))
      (node (ref "U7") (pin "7") (pinfunction "+VS_7") (pintype "power_in"))
    )
    (net (code "50") (name "RFgnd") (class "Default")
      (node (ref "C60") (pin "1") (pinfunction "1_1") (pintype "passive"))
      (node (ref "CT1") (pin "5") (pinfunction "5_5") (pintype "passive"))
      (node (ref "CT1") (pin "6") (pinfunction "6_6") (pintype "passive"))
      (node (ref "J5") (pin "2") (pinfunction "2_2") (pintype "passive"))
      (node (ref "J5") (pin "3") (pinfunction "3_3") (pintype "passive"))
      (node (ref "J5") (pin "4") (pinfunction "4_4") (pintype "passive"))
      (node (ref "J5") (pin "5") (pinfunction "5_5") (pintype "passive"))
      (node (ref "MH6") (pin "1") (pinfunction "MH_1") (pintype "passive"))
      (node (ref "P5") (pin "2") (pinfunction "2_2") (pintype "passive"))
      (node (ref "R86") (pin "2") (pinfunction "2_2") (pintype "passive"))
    )
    (net (code "51") (name "Vd") (class "Default")
      (node (ref "R60") (pin "1") (pinfunction "1_1") (pintype "passive"))
      (node (ref "R65") (pin "1") (pinfunction "1_1") (pintype "passive"))
      (node (ref "R66") (pin "1") (pinfunction "1_1") (pintype "passive"))
      (node (ref "R67") (pin "1") (pinfunction "1_1") (pintype "passive"))
      (node (ref "R68") (pin "1") (pinfunction "1_1") (pintype "passive"))
      (node (ref "R76") (pin "1") (pinfunction "1_1") (pintype "passive"))
      (node (ref "R77") (pin "1") (pinfunction "1_1") (pintype "passive"))
      (node (ref "R79") (pin "1") (pinfunction "1_1") (pintype "passive"))
      (node (ref "R81") (pin "1") (pinfunction "1_1") (pintype "passive"))
      (node (ref "R82") (pin "1") (pinfunction "1_1") (pintype "passive"))
      (node (ref "R85") (pin "1") (pinfunction "1_1") (pintype "passive"))
      (node (ref "R87") (pin "1") (pinfunction "1_1") (pintype "passive"))
      (node (ref "R93") (pin "1") (pinfunction "1_1") (pintype "passive"))
    )
    (net (code "52") (name "unconnected-(CT1-Pad7)") (class "Default")
      (node (ref "CT1") (pin "7") (pinfunction "7_7") (pintype "passive+no_connect"))
    )
    (net (code "53") (name "unconnected-(CT1-Pad8)") (class "Default")
      (node (ref "CT1") (pin "8") (pinfunction "8_8") (pintype "passive+no_connect"))
    )
    (net (code "54") (name "unconnected-(U6B-+V-Pad8)") (class "Default")
      (node (ref "U6") (pin "8") (pinfunction "+V_8") (pintype "power_in+no_connect"))
    )
    (net (code "55") (name "unconnected-(U6B--V-Pad4)") (class "Default")
      (node (ref "U6") (pin "4") (pinfunction "-V_4") (pintype "power_in+no_connect"))
    )
    (net (code "56") (name "unconnected-(U8-NC-Pad3)") (class "Default")
      (node (ref "U8") (pin "3") (pinfunction "NC_3") (pintype "passive+no_connect"))
    )
  )
)
